# OV2640.net
KiCad netlist of a schematic drawn in Altium Designer
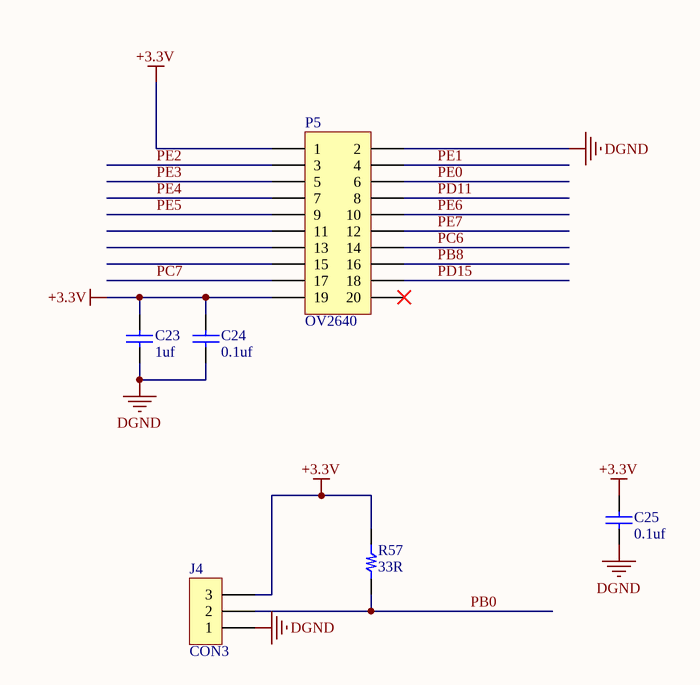
[diagram p0: OV2640.SchDoc]

(export (version "E")
  (design (tool "Eeschema 10.0.6"))
  (components
    (comp (ref "C23")
      (value "1uf")
      (footprint "0805C")
      (description "贴片电容")
      (fields (field (name "PUBLISHER") "Altium Limited"))
      (libsource (lib "Device_CHT") (part "Cap"))
    )
    (comp (ref "C24")
      (value "0.1uf")
      (footprint "0805C")
      (description "贴片电容")
      (fields (field (name "PUBLISHER") "Altium Limited"))
      (libsource (lib "Device_CHT") (part "Cap"))
    )
    (comp (ref "C25")
      (value "0.1uf")
      (footprint "0805C")
      (description "贴片电容")
      (fields (field (name "PUBLISHER") "Altium Limited"))
      (libsource (lib "Device_CHT") (part "Cap"))
    )
    (comp (ref "J4")
      (value "CON3")
      (footprint "HDR1X3-2.54MM")
      (description "Connector")
      (libsource (lib "Connector_Veiko") (part "CON3"))
    )
    (comp (ref "P5")
      (value "OV2640")
      (footprint "HDR2X10-2.54MM")
      (description "Header, 10-Pin, Dual row")
      (fields (field (name "PUBLISHER") "Altium Limited"))
      (libsource (lib "Connector_Veiko") (part "CON10X2"))
    )
    (comp (ref "R57")
      (value "33R")
      (footprint "0805_small")
      (description "电阻")
      (fields (field (name "PUBLISHER") "Altium Limited"))
      (libsource (lib "Device_CHT") (part "Res"))
    )
  )
  (nets
    (net (code "1") (name "+3.3V") (class "Default")
      (node (ref "C23") (pin "1") (pinfunction "1_1") (pintype "passive"))
      (node (ref "C24") (pin "1") (pinfunction "1_1") (pintype "passive"))
      (node (ref "C25") (pin "1") (pinfunction "1_1") (pintype "passive"))
      (node (ref "J4") (pin "3") (pinfunction "3_3") (pintype "passive"))
      (node (ref "P5") (pin "1") (pinfunction "1_1") (pintype "passive"))
      (node (ref "P5") (pin "19") (pinfunction "19_19") (pintype "passive"))
      (node (ref "R57") (pin "1") (pinfunction "1_1") (pintype "passive"))
    )
    (net (code "2") (name "/PB0") (class "Default")
      (node (ref "J4") (pin "2") (pinfunction "2_2") (pintype "passive"))
      (node (ref "R57") (pin "2") (pinfunction "2_2") (pintype "passive"))
    )
    (net (code "3") (name "/PB8") (class "Default")
      (node (ref "P5") (pin "16") (pinfunction "16_16") (pintype "passive"))
    )
    (net (code "4") (name "/PC6") (class "Default")
      (node (ref "P5") (pin "14") (pinfunction "14_14") (pintype "passive"))
    )
    (net (code "5") (name "/PC7") (class "Default")
      (node (ref "P5") (pin "17") (pinfunction "17_17") (pintype "passive"))
    )
    (net (code "6") (name "/PD11") (class "Default")
      (node (ref "P5") (pin "8") (pinfunction "8_8") (pintype "passive"))
    )
    (net (code "7") (name "/PD15") (class "Default")
      (node (ref "P5") (pin "18") (pinfunction "18_18") (pintype "passive"))
    )
    (net (code "8") (name "/PE0") (class "Default")
      (node (ref "P5") (pin "6") (pinfunction "6_6") (pintype "passive"))
    )
    (net (code "9") (name "/PE1") (class "Default")
      (node (ref "P5") (pin "4") (pinfunction "4_4") (pintype "passive"))
    )
    (net (code "10") (name "/PE2") (class "Default")
      (node (ref "P5") (pin "3") (pinfunction "3_3") (pintype "passive"))
    )
    (net (code "11") (name "/PE3") (class "Default")
      (node (ref "P5") (pin "5") (pinfunction "5_5") (pintype "passive"))
    )
    (net (code "12") (name "/PE4") (class "Default")
      (node (ref "P5") (pin "7") (pinfunction "7_7") (pintype "passive"))
    )
    (net (code "13") (name "/PE5") (class "Default")
      (node (ref "P5") (pin "9") (pinfunction "9_9") (pintype "passive"))
    )
    (net (code "14") (name "/PE6") (class "Default")
      (node (ref "P5") (pin "10") (pinfunction "10_10") (pintype "passive"))
    )
    (net (code "15") (name "/PE7") (class "Default")
      (node (ref "P5") (pin "12") (pinfunction "12_12") (pintype "passive"))
    )
    (net (code "16") (name "DGND") (class "Default")
      (node (ref "C23") (pin "2") (pinfunction "2_2") (pintype "passive"))
      (node (ref "C24") (pin "2") (pinfunction "2_2") (pintype "passive"))
      (node (ref "C25") (pin "2") (pinfunction "2_2") (pintype "passive"))
      (node (ref "J4") (pin "1") (pinfunction "1_1") (pintype "passive"))
      (node (ref "P5") (pin "2") (pinfunction "2_2") (pintype "passive"))
    )
    (net (code "17") (name "unconnected-(P5-Pad11)") (class "Default")
      (node (ref "P5") (pin "11") (pinfunction "11_11") (pintype "passive"))
    )
    (net (code "18") (name "unconnected-(P5-Pad13)") (class "Default")
      (node (ref "P5") (pin "13") (pinfunction "13_13") (pintype "passive"))
    )
    (net (code "19") (name "unconnected-(P5-Pad15)") (class "Default")
      (node (ref "P5") (pin "15") (pinfunction "15_15") (pintype "passive"))
    )
    (net (code "20") (name "unconnected-(P5-Pad20)") (class "Default")
      (node (ref "P5") (pin "20") (pinfunction "20_20") (pintype "passive+no_connect"))
    )
  )
)
